# IR_Interruptor_board.net
KiCad netlist of a schematic drawn in EAGLE
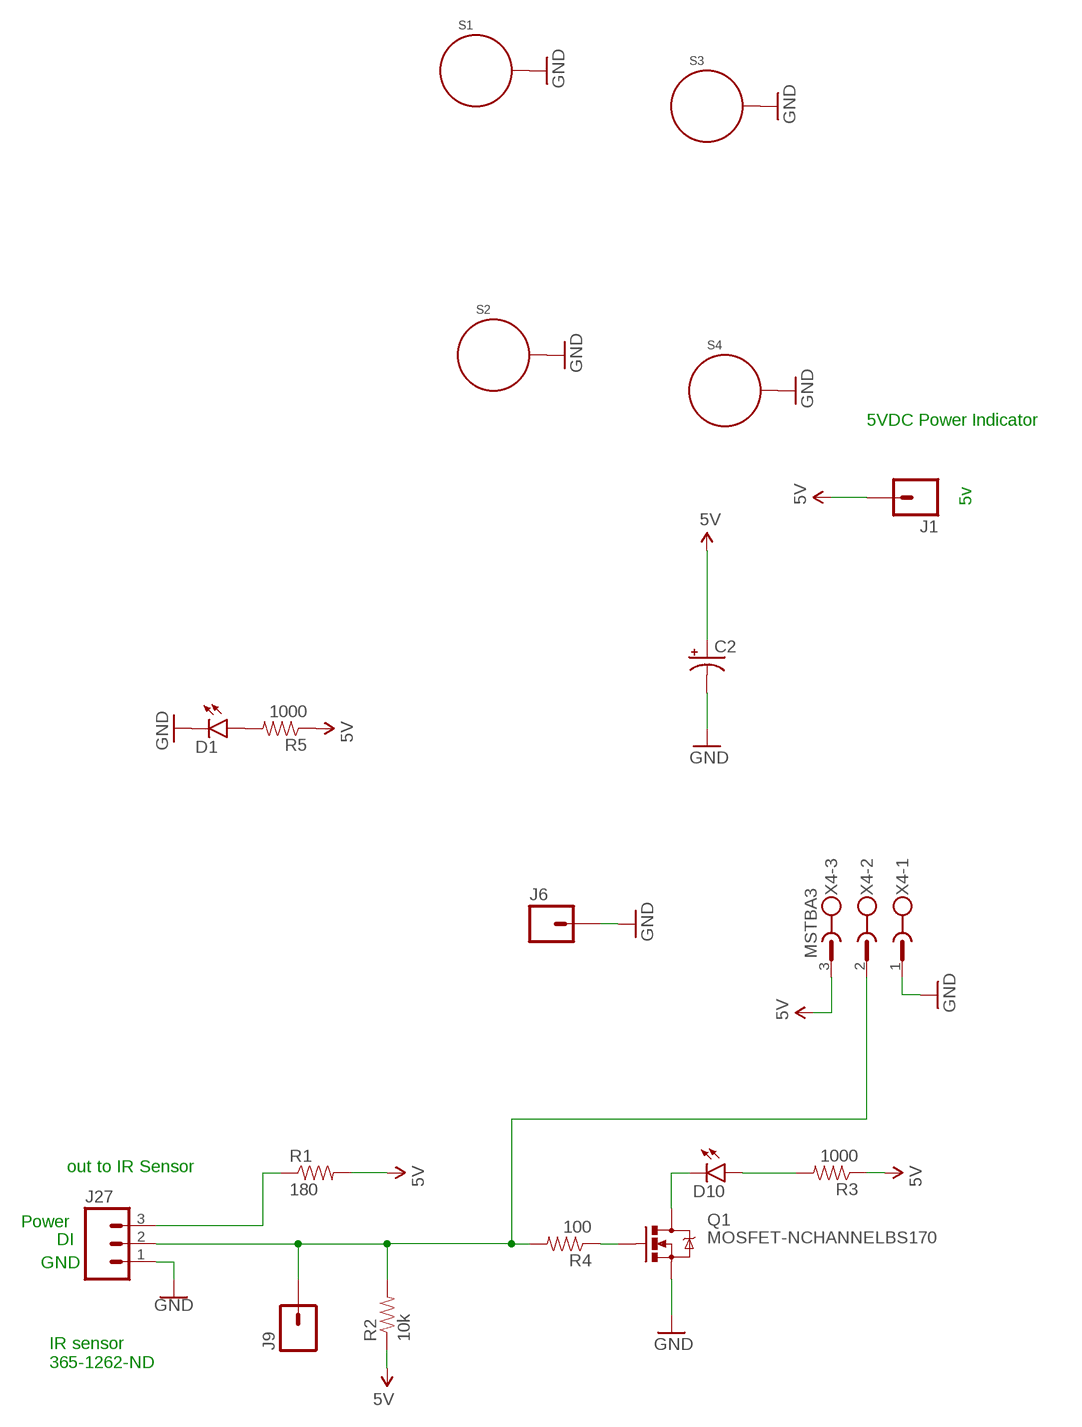
[diagram p0: schematic, sheet 1]

(export (version "E")
  (design (tool "Eeschema 10.0.6"))
  (components
    (comp (ref "C2")
      (value "CAP_POLPTH2")
      (footprint "eagle-import:CPOL-RADIAL-10UF-25V")
      (libsource (lib "eagle-import") (part "CAP_POLPTH2"))
    )
    (comp (ref "D1")
      (value "LED1206")
      (footprint "eagle-import:LED-1206")
      (libsource (lib "eagle-import") (part "LED1206"))
    )
    (comp (ref "D10")
      (value "LED1206")
      (footprint "eagle-import:LED-1206")
      (libsource (lib "eagle-import") (part "LED1206"))
    )
    (comp (ref "J1")
      (value "M01PTH")
      (footprint "eagle-import:1X01")
      (libsource (lib "eagle-import") (part "M01PTH"))
    )
    (comp (ref "J6")
      (value "M01PTH")
      (footprint "eagle-import:1X01")
      (libsource (lib "eagle-import") (part "M01PTH"))
    )
    (comp (ref "J9")
      (value "M01PTH")
      (footprint "eagle-import:1X01")
      (libsource (lib "eagle-import") (part "M01PTH"))
    )
    (comp (ref "J27")
      (value "M03SCREW")
      (footprint "eagle-import:SCREWTERMINAL-3.5MM-3")
      (libsource (lib "eagle-import") (part "M03SCREW"))
    )
    (comp (ref "Q1")
      (value "MOSFET-NCHANNELBS170")
      (footprint "eagle-import:TO-92")
      (libsource (lib "eagle-import") (part "MOSFET-NCHANNELBS170"))
    )
    (comp (ref "R1")
      (value "180")
      (footprint "eagle-import:0805")
      (libsource (lib "eagle-import") (part "RESISTOR0805-RES"))
    )
    (comp (ref "R2")
      (value "10k")
      (footprint "eagle-import:0805")
      (libsource (lib "eagle-import") (part "RESISTOR0805-RES"))
    )
    (comp (ref "R3")
      (value "1000")
      (footprint "eagle-import:0805")
      (libsource (lib "eagle-import") (part "RESISTOR0805-RES"))
    )
    (comp (ref "R4")
      (value "100")
      (footprint "eagle-import:0805")
      (libsource (lib "eagle-import") (part "RESISTOR0805-RES"))
    )
    (comp (ref "R5")
      (value "1000")
      (footprint "eagle-import:0805")
      (libsource (lib "eagle-import") (part "RESISTOR0805-RES"))
    )
    (comp (ref "S1")
      (value "STANDOFF_ELECTRICAL")
      (footprint "eagle-import:STANDOFF-ELECTRICAL")
      (fields (field (name "SPICEPREFIX") "X"))
      (libsource (lib "eagle-import") (part "STANDOFF_ELECTRICAL"))
    )
    (comp (ref "S2")
      (value "STANDOFF_ELECTRICAL")
      (footprint "eagle-import:STANDOFF-ELECTRICAL")
      (fields (field (name "SPICEPREFIX") "X"))
      (libsource (lib "eagle-import") (part "STANDOFF_ELECTRICAL"))
    )
    (comp (ref "S3")
      (value "STANDOFF_ELECTRICAL")
      (footprint "eagle-import:STANDOFF-ELECTRICAL")
      (fields (field (name "SPICEPREFIX") "X"))
      (libsource (lib "eagle-import") (part "STANDOFF_ELECTRICAL"))
    )
    (comp (ref "S4")
      (value "STANDOFF_ELECTRICAL")
      (footprint "eagle-import:STANDOFF-ELECTRICAL")
      (fields (field (name "SPICEPREFIX") "X"))
      (libsource (lib "eagle-import") (part "STANDOFF_ELECTRICAL"))
    )
    (comp (ref "X4")
      (value "MSTBA3")
      (footprint "eagle-import:MSTBA3")
      (fields (field (name "MF") "FARNELL") (field (name "MPN") "1757255"))
      (libsource (lib "eagle-import") (part "MSTBA3"))
    )
  )
  (nets
    (net (code "1") (name "5V") (class "Default")
      (node (ref "C2") (pin "1") (pinfunction "+_1") (pintype "passive"))
      (node (ref "J1") (pin "1") (pinfunction "1_1") (pintype "passive"))
      (node (ref "R1") (pin "2") (pinfunction "2_2") (pintype "passive"))
      (node (ref "R2") (pin "1") (pinfunction "1_1") (pintype "passive"))
      (node (ref "R3") (pin "1") (pinfunction "1_1") (pintype "passive"))
      (node (ref "R5") (pin "1") (pinfunction "1_1") (pintype "passive"))
      (node (ref "X4") (pin "3") (pinfunction "1_3") (pintype "passive"))
    )
    (net (code "2") (name "GND") (class "Default")
      (node (ref "C2") (pin "2") (pinfunction "-_2") (pintype "passive"))
      (node (ref "D1") (pin "C") (pinfunction "C_C") (pintype "passive"))
      (node (ref "J27") (pin "1") (pinfunction "1_1") (pintype "passive"))
      (node (ref "J6") (pin "1") (pinfunction "1_1") (pintype "passive"))
      (node (ref "Q1") (pin "3") (pinfunction "S_3") (pintype "passive"))
      (node (ref "S1") (pin "P1") (pinfunction "P$1_P1") (pintype "bidirectional"))
      (node (ref "S2") (pin "P1") (pinfunction "P$1_P1") (pintype "bidirectional"))
      (node (ref "S3") (pin "P1") (pinfunction "P$1_P1") (pintype "bidirectional"))
      (node (ref "S4") (pin "P1") (pinfunction "P$1_P1") (pintype "bidirectional"))
      (node (ref "X4") (pin "1") (pinfunction "1_1") (pintype "passive"))
    )
    (net (code "3") (name "Net-(D1-PadA)") (class "Default")
      (node (ref "D1") (pin "A") (pinfunction "A_A") (pintype "passive"))
      (node (ref "R5") (pin "2") (pinfunction "2_2") (pintype "passive"))
    )
    (net (code "4") (name "Net-(D10-PadA)") (class "Default")
      (node (ref "D10") (pin "A") (pinfunction "A_A") (pintype "passive"))
      (node (ref "R3") (pin "2") (pinfunction "2_2") (pintype "passive"))
    )
    (net (code "5") (name "Net-(J27-Pad3)") (class "Default")
      (node (ref "J27") (pin "3") (pinfunction "3_3") (pintype "passive"))
      (node (ref "R1") (pin "1") (pinfunction "1_1") (pintype "passive"))
    )
    (net (code "6") (name "Net-(Q1-D)") (class "Default")
      (node (ref "D10") (pin "C") (pinfunction "C_C") (pintype "passive"))
      (node (ref "Q1") (pin "1") (pinfunction "D_1") (pintype "passive"))
    )
    (net (code "7") (name "Net-(Q1-G)") (class "Default")
      (node (ref "Q1") (pin "2") (pinfunction "G_2") (pintype "passive"))
      (node (ref "R4") (pin "1") (pinfunction "1_1") (pintype "passive"))
    )
    (net (code "8") (name "Net-(X4B-1)") (class "Default")
      (node (ref "J27") (pin "2") (pinfunction "2_2") (pintype "passive"))
      (node (ref "J9") (pin "1") (pinfunction "1_1") (pintype "passive"))
      (node (ref "R2") (pin "2") (pinfunction "2_2") (pintype "passive"))
      (node (ref "R4") (pin "2") (pinfunction "2_2") (pintype "passive"))
      (node (ref "X4") (pin "2") (pinfunction "1_2") (pintype "passive"))
    )
  )
)
